# FT65E_SATA.net
KiCad netlist of a schematic drawn in Altium Designer
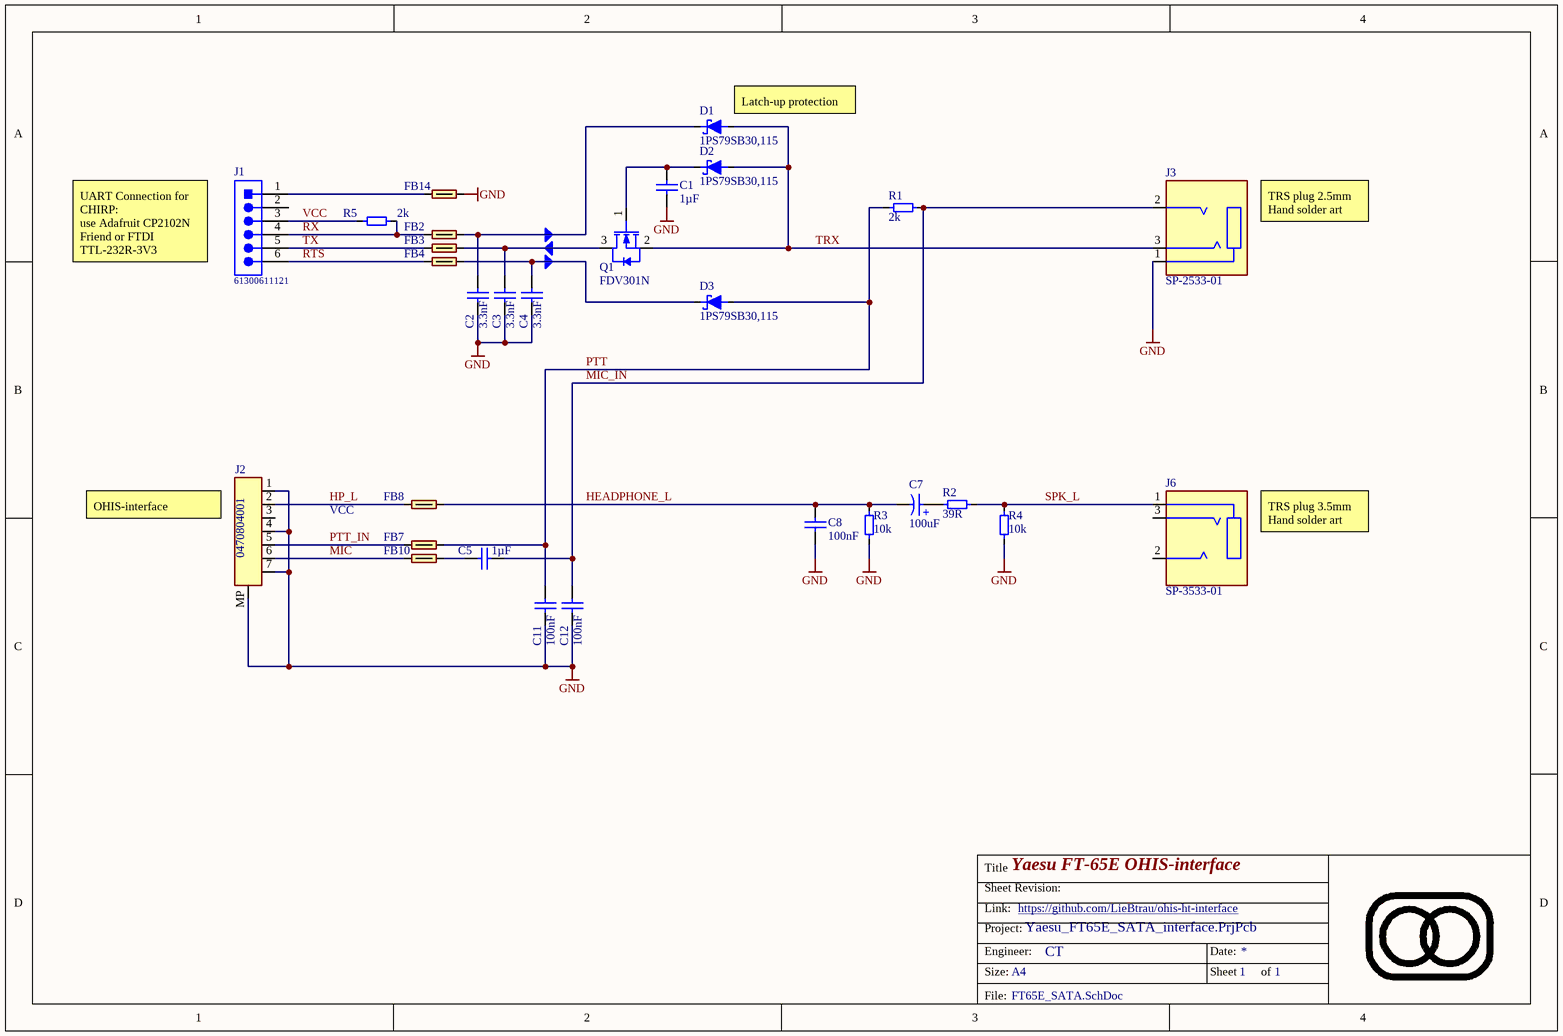
[diagram p0: FT65E_SATA.SchDoc]

(export (version "E")
  (design (tool "Eeschema 10.0.6"))
  (components
    (comp (ref "C1")
      (value "1µF")
      (footprint "0805-C-N")
      (description "WCAP-CSGP Multilayer Ceramic Chip Capacitor, General Purpose, size 0805, X7R, 1µF, 10VDC")
      (fields (field (name "TOLERANCE") "10%") (field (name "JLCPCB PART #") "C28323"))
      (libsource (lib "7c7 Engineering") (part "CAP-NP-2"))
    )
    (comp (ref "C2")
      (value "3.3nF")
      (footprint "0603-C-N")
      (description "WCAP-CSGP Multilayer Ceramic Chip Capacitor, General Purpose, size 0603, X7R, 3.3nF, 50VDC")
      (fields (field (name "TOLERANCE") "10%") (field (name "Comment") "Capacitor 3.3nF +/-10% 50V X7R 0603"))
      (libsource (lib "7c7 Engineering") (part "CAP-NP-2"))
    )
    (comp (ref "C3")
      (value "3.3nF")
      (footprint "0603-C-N")
      (description "WCAP-CSGP Multilayer Ceramic Chip Capacitor, General Purpose, size 0603, X7R, 3.3nF, 50VDC")
      (fields (field (name "TOLERANCE") "10%") (field (name "Comment") "Capacitor 3.3nF +/-10% 50V X7R 0603"))
      (libsource (lib "7c7 Engineering") (part "CAP-NP-2"))
    )
    (comp (ref "C4")
      (value "3.3nF")
      (footprint "0603-C-N")
      (description "WCAP-CSGP Multilayer Ceramic Chip Capacitor, General Purpose, size 0603, X7R, 3.3nF, 50VDC")
      (fields (field (name "TOLERANCE") "10%") (field (name "Comment") "Capacitor 3.3nF +/-10% 50V X7R 0603"))
      (libsource (lib "7c7 Engineering") (part "CAP-NP-2"))
    )
    (comp (ref "C5")
      (value "1µF")
      (footprint "0805-C-N")
      (description "WCAP-CSGP Multilayer Ceramic Chip Capacitor, General Purpose, size 0805, X7R, 1µF, 10VDC")
      (fields (field (name "TOLERANCE") "10%") (field (name "JLCPCB PART #") "C28323"))
      (libsource (lib "7c7 Engineering") (part "CAP-NP-2"))
    )
    (comp (ref "C7")
      (value "865080142007")
      (footprint "WCAP-ASLI_D5H5.5")
      (description "WCAP-ASLI Aluminum Electrolytic Capacitor, V-Chip, D5 x H5.5mm, 100uF, 6.3V")
      (fields (field (name "CAPACITANCE") "100uF") (field (name "MANUFACTURER") "Wurth Elektronik"))
      (libsource (lib "7c7 Engineering") (part "865081763011"))
    )
    (comp (ref "C8")
      (value "100nF")
      (footprint "0603-C-N")
      (description "Capacitor MLCC, General Purpose, size 0603, X7R, 100nF, +/-10%, 50V")
      (fields (field (name "JLCPCB PART #") "C14663") (field (name "TOLERANCE") "10%"))
      (libsource (lib "7c7 Engineering") (part "CAP-NP-2"))
    )
    (comp (ref "C11")
      (value "100nF")
      (footprint "0603-C-N")
      (description "Capacitor MLCC, General Purpose, size 0603, X7R, 100nF, +/-10%, 50V")
      (fields (field (name "JLCPCB PART #") "C14663") (field (name "TOLERANCE") "10%"))
      (libsource (lib "7c7 Engineering") (part "CAP-NP-2"))
    )
    (comp (ref "C12")
      (value "100nF")
      (footprint "0603-C-N")
      (description "Capacitor MLCC, General Purpose, size 0603, X7R, 100nF, +/-10%, 50V")
      (fields (field (name "JLCPCB PART #") "C14663") (field (name "TOLERANCE") "10%"))
      (libsource (lib "7c7 Engineering") (part "CAP-NP-2"))
    )
    (comp (ref "D1")
      (value "1PS79SB30,115")
      (footprint "FP-SOD523-MFG")
      (description "VR=40V IF=200mA 20pF")
      (fields (field (name "JLCPCB PART #") "C426690"))
      (libsource (lib "7c7 Engineering") (part "DIODE-SKY-2"))
    )
    (comp (ref "D2")
      (value "1PS79SB30,115")
      (footprint "FP-SOD523-MFG")
      (description "VR=40V IF=200mA 20pF")
      (fields (field (name "JLCPCB PART #") "C426690"))
      (libsource (lib "7c7 Engineering") (part "DIODE-SKY-2"))
    )
    (comp (ref "D3")
      (value "1PS79SB30,115")
      (footprint "FP-SOD523-MFG")
      (description "VR=40V IF=200mA 20pF")
      (fields (field (name "JLCPCB PART #") "C426690"))
      (libsource (lib "7c7 Engineering") (part "DIODE-SKY-2"))
    )
    (comp (ref "FB2")
      (value "742861210")
      (footprint "0603-FB-N")
      (description "Ferrite Beads Multi-Layer 1KOhm 25% 100MHz 50mA 1.8Ohm DCR 0603 T/R")
      (fields (field (name "TOLERANCE") "25%"))
      (libsource (lib "7c7 Engineering") (part "IND_BEAD"))
    )
    (comp (ref "FB3")
      (value "742861210")
      (footprint "0603-FB-N")
      (description "Ferrite Beads Multi-Layer 1KOhm 25% 100MHz 50mA 1.8Ohm DCR 0603 T/R")
      (fields (field (name "TOLERANCE") "25%"))
      (libsource (lib "7c7 Engineering") (part "IND_BEAD"))
    )
    (comp (ref "FB4")
      (value "742861210")
      (footprint "0603-FB-N")
      (description "Ferrite Beads Multi-Layer 1KOhm 25% 100MHz 50mA 1.8Ohm DCR 0603 T/R")
      (fields (field (name "TOLERANCE") "25%"))
      (libsource (lib "7c7 Engineering") (part "IND_BEAD"))
    )
    (comp (ref "FB7")
      (value "742861210")
      (footprint "0603-FB-N")
      (description "Ferrite Beads Multi-Layer 1KOhm 25% 100MHz 50mA 1.8Ohm DCR 0603 T/R")
      (fields (field (name "TOLERANCE") "25%"))
      (libsource (lib "7c7 Engineering") (part "IND_BEAD"))
    )
    (comp (ref "FB8")
      (value "742861210")
      (footprint "0603-FB-N")
      (description "Ferrite Beads Multi-Layer 1KOhm 25% 100MHz 50mA 1.8Ohm DCR 0603 T/R")
      (fields (field (name "TOLERANCE") "25%"))
      (libsource (lib "7c7 Engineering") (part "IND_BEAD"))
    )
    (comp (ref "FB10")
      (value "742861210")
      (footprint "0603-FB-N")
      (description "Ferrite Beads Multi-Layer 1KOhm 25% 100MHz 50mA 1.8Ohm DCR 0603 T/R")
      (fields (field (name "TOLERANCE") "25%"))
      (libsource (lib "7c7 Engineering") (part "IND_BEAD"))
    )
    (comp (ref "FB14")
      (value "742861210")
      (footprint "0603-FB-N")
      (description "Ferrite Beads Multi-Layer 1KOhm 25% 100MHz 50mA 1.8Ohm DCR 0603 T/R")
      (fields (field (name "TOLERANCE") "25%"))
      (libsource (lib "7c7 Engineering") (part "IND_BEAD"))
    )
    (comp (ref "J1")
      (value "61300611121")
      (footprint "61300611121")
      (description "WR-PHD Pin Header, THT, pitch 2.54mm, Single Row, Vertical, 6p")
      (fields (field (name "MANUFACTURER") "Wurth Elektronik"))
      (libsource (lib "7c7 Engineering") (part "Symbol"))
    )
    (comp (ref "J2")
      (value "0470804001")
      (footprint "0470804001-Footprint-1")
      (description "Header Connector, pcb Mount, recept, 7 Contacts, pin, 0.05 Pitch, surface Mount Terminal, locking")
      (fields (field (name "JLCPCB PART #") "C587821"))
      (libsource (lib "7c7 Engineering") (part "CN_HDR_1x7P"))
    )
    (comp (ref "J3")
      (value "SP-2533-01")
      (footprint "SP-2533-01-Footprint-1")
      (description "2.5 mm, Stereo, Overmold, Audio Plug Connector")
      (libsource (lib "") (part "CN_AUDIO_JACK_TRS_NO_SWITCH_1"))
    )
    (comp (ref "J6")
      (value "SP-3533-01")
      (footprint "SP-3533-01-Footprint-1")
      (description "3.5 mm, Stereo, Overmold, Audio Plug Connector")
      (libsource (lib "7c7 Engineering") (part "CN_AUDIO_JACK_TRS_NO_SWITCH"))
    )
    (comp (ref "Q1")
      (value "FDV301N")
      (footprint "SOT-23-3-N")
      (description "Transistor MOSFET N-Ch. 25V 220mA 0, 35W 4Ohm SOT23")
      (fields (field (name "JLCPCB PART #") "C15310"))
      (libsource (lib "7c7 Engineering") (part "NEMOS-GSD-3"))
    )
    (comp (ref "R1")
      (value "2k")
      (footprint "0603-R-N")
      (description "Chip Resistor, Thick Film, General Purpose, 0603, 100mW, 50V, 2 kOhm, +/-1%")
      (fields (field (name "JLCPCB PART #") "C22975") (field (name "TOLERANCE") "1%"))
      (libsource (lib "") (part "RES_1"))
    )
    (comp (ref "R2")
      (value "39R")
      (footprint "0603-R-N")
      (description "SMD Chip Resistor, 39 Ohm, ± 1%, 100 mW, 0603 [1608 Metric], Thick Film, General Purpose")
      (fields (field (name "TOLERANCE") "1%") (field (name "JLCPCB PART #") "C2907161"))
      (libsource (lib "") (part "RES_1"))
    )
    (comp (ref "R3")
      (value "10k")
      (footprint "0603-R-N")
      (description "Chip Resistor, Thick Film, General Purpose, 0603, 100mW, 50V, 10 kOhm, +/-1%")
      (fields (field (name "JLCPCB PART #") "C25804") (field (name "TOLERANCE") "1%"))
      (libsource (lib "7c7 Engineering") (part "RES"))
    )
    (comp (ref "R4")
      (value "10k")
      (footprint "0603-R-N")
      (description "Chip Resistor, Thick Film, General Purpose, 0603, 100mW, 50V, 10 kOhm, +/-1%")
      (fields (field (name "JLCPCB PART #") "C25804") (field (name "TOLERANCE") "1%"))
      (libsource (lib "7c7 Engineering") (part "RES"))
    )
    (comp (ref "R5")
      (value "2k")
      (footprint "0603-R-N")
      (description "Chip Resistor, Thick Film, General Purpose, 0603, 100mW, 50V, 2 kOhm, +/-1%")
      (fields (field (name "JLCPCB PART #") "C22975") (field (name "TOLERANCE") "1%"))
      (libsource (lib "") (part "RES_1"))
    )
  )
  (nets
    (net (code "1") (name "/HEADPHONE_L") (class "Default")
      (node (ref "C7") (pin "2") (pinfunction "N_2") (pintype "passive"))
      (node (ref "C8") (pin "2") (pinfunction "2_2") (pintype "passive"))
      (node (ref "FB8") (pin "2") (pinfunction "2_2") (pintype "passive"))
      (node (ref "R3") (pin "2") (pinfunction "2_2") (pintype "passive"))
    )
    (net (code "2") (name "/HP_L") (class "Default")
      (node (ref "FB8") (pin "1") (pinfunction "1_1") (pintype "passive"))
      (node (ref "J2") (pin "2") (pinfunction "2_2") (pintype "power_in"))
    )
    (net (code "3") (name "/MIC") (class "Default")
      (node (ref "FB10") (pin "1") (pinfunction "1_1") (pintype "passive"))
      (node (ref "J2") (pin "6") (pinfunction "6_6") (pintype "power_in"))
    )
    (net (code "4") (name "/MIC_IN") (class "Default")
      (node (ref "C12") (pin "2") (pinfunction "2_2") (pintype "passive"))
      (node (ref "C5") (pin "1") (pinfunction "1_1") (pintype "passive"))
      (node (ref "J3") (pin "2") (pinfunction "2_2") (pintype "passive"))
      (node (ref "R1") (pin "2") (pinfunction "2_2") (pintype "passive"))
    )
    (net (code "5") (name "/PTT") (class "Default")
      (node (ref "C11") (pin "2") (pinfunction "2_2") (pintype "passive"))
      (node (ref "D3") (pin "2") (pinfunction "A_2") (pintype "passive"))
      (node (ref "FB7") (pin "2") (pinfunction "2_2") (pintype "passive"))
      (node (ref "R1") (pin "1") (pinfunction "1_1") (pintype "passive"))
    )
    (net (code "6") (name "/PTT_IN") (class "Default")
      (node (ref "FB7") (pin "1") (pinfunction "1_1") (pintype "passive"))
      (node (ref "J2") (pin "5") (pinfunction "5_5") (pintype "power_in"))
    )
    (net (code "7") (name "/RTS") (class "Default")
      (node (ref "FB4") (pin "1") (pinfunction "1_1") (pintype "passive"))
      (node (ref "J1") (pin "6") (pinfunction "6_6") (pintype "passive"))
    )
    (net (code "8") (name "/RX") (class "Default")
      (node (ref "FB2") (pin "1") (pinfunction "1_1") (pintype "passive"))
      (node (ref "J1") (pin "4") (pinfunction "4_4") (pintype "passive"))
      (node (ref "R5") (pin "2") (pinfunction "2_2") (pintype "passive"))
    )
    (net (code "9") (name "/SPK_L") (class "Default")
      (node (ref "J6") (pin "1") (pinfunction "1_1") (pintype "passive"))
      (node (ref "R2") (pin "2") (pinfunction "2_2") (pintype "passive"))
      (node (ref "R4") (pin "2") (pinfunction "2_2") (pintype "passive"))
    )
    (net (code "10") (name "/TRX") (class "Default")
      (node (ref "D1") (pin "2") (pinfunction "A_2") (pintype "passive"))
      (node (ref "D2") (pin "2") (pinfunction "A_2") (pintype "passive"))
      (node (ref "J3") (pin "3") (pinfunction "3_3") (pintype "passive"))
      (node (ref "Q1") (pin "2") (pinfunction "S_2") (pintype "passive"))
    )
    (net (code "11") (name "/TX") (class "Default")
      (node (ref "FB3") (pin "1") (pinfunction "1_1") (pintype "passive"))
      (node (ref "J1") (pin "5") (pinfunction "5_5") (pintype "passive"))
    )
    (net (code "12") (name "/VCC") (class "Default")
      (node (ref "J1") (pin "3") (pinfunction "3_3") (pintype "passive"))
      (node (ref "R5") (pin "1") (pinfunction "1_1") (pintype "passive"))
    )
    (net (code "13") (name "GND") (class "Default")
      (node (ref "C1") (pin "1") (pinfunction "1_1") (pintype "passive"))
      (node (ref "C11") (pin "1") (pinfunction "1_1") (pintype "passive"))
      (node (ref "C12") (pin "1") (pinfunction "1_1") (pintype "passive"))
      (node (ref "C2") (pin "1") (pinfunction "1_1") (pintype "passive"))
      (node (ref "C3") (pin "1") (pinfunction "1_1") (pintype "passive"))
      (node (ref "C4") (pin "1") (pinfunction "1_1") (pintype "passive"))
      (node (ref "C8") (pin "1") (pinfunction "1_1") (pintype "passive"))
      (node (ref "FB14") (pin "2") (pinfunction "2_2") (pintype "passive"))
      (node (ref "J2") (pin "1") (pinfunction "1_1") (pintype "power_in"))
      (node (ref "J2") (pin "4") (pinfunction "4_4") (pintype "power_in"))
      (node (ref "J2") (pin "7") (pinfunction "7_7") (pintype "power_in"))
      (node (ref "J2") (pin "MP") (pinfunction "MP_MP") (pintype "power_in"))
      (node (ref "J3") (pin "1") (pinfunction "1_1") (pintype "passive"))
      (node (ref "R3") (pin "1") (pinfunction "1_1") (pintype "passive"))
      (node (ref "R4") (pin "1") (pinfunction "1_1") (pintype "passive"))
    )
    (net (code "14") (name "Net-(C5-Pad2)") (class "Default")
      (node (ref "C5") (pin "2") (pinfunction "2_2") (pintype "passive"))
      (node (ref "FB10") (pin "2") (pinfunction "2_2") (pintype "passive"))
    )
    (net (code "15") (name "Net-(C7-P)") (class "Default")
      (node (ref "C7") (pin "1") (pinfunction "P_1") (pintype "passive"))
      (node (ref "R2") (pin "1") (pinfunction "1_1") (pintype "passive"))
    )
    (net (code "16") (name "Net-(D1-K)") (class "Default")
      (node (ref "C2") (pin "2") (pinfunction "2_2") (pintype "passive"))
      (node (ref "D1") (pin "1") (pinfunction "K_1") (pintype "passive"))
      (node (ref "FB2") (pin "2") (pinfunction "2_2") (pintype "passive"))
    )
    (net (code "17") (name "Net-(D2-K)") (class "Default")
      (node (ref "C1") (pin "2") (pinfunction "2_2") (pintype "passive"))
      (node (ref "D2") (pin "1") (pinfunction "K_1") (pintype "passive"))
      (node (ref "Q1") (pin "1") (pinfunction "G_1") (pintype "passive"))
    )
    (net (code "18") (name "Net-(D3-K)") (class "Default")
      (node (ref "C4") (pin "2") (pinfunction "2_2") (pintype "passive"))
      (node (ref "D3") (pin "1") (pinfunction "K_1") (pintype "passive"))
      (node (ref "FB4") (pin "2") (pinfunction "2_2") (pintype "passive"))
    )
    (net (code "19") (name "Net-(FB14-Pad1)") (class "Default")
      (node (ref "FB14") (pin "1") (pinfunction "1_1") (pintype "passive"))
      (node (ref "J1") (pin "1") (pinfunction "1_1") (pintype "passive"))
    )
    (net (code "20") (name "Net-(Q1-D)") (class "Default")
      (node (ref "C3") (pin "2") (pinfunction "2_2") (pintype "passive"))
      (node (ref "FB3") (pin "2") (pinfunction "2_2") (pintype "passive"))
      (node (ref "Q1") (pin "3") (pinfunction "D_3") (pintype "passive"))
    )
    (net (code "21") (name "unconnected-(J1-Pad2)") (class "Default")
      (node (ref "J1") (pin "2") (pinfunction "2_2") (pintype "passive"))
    )
    (net (code "22") (name "unconnected-(J2-Pad3)") (class "Default")
      (node (ref "J2") (pin "3") (pinfunction "3_3") (pintype "power_in"))
    )
    (net (code "23") (name "unconnected-(J6-Pad2)") (class "Default")
      (node (ref "J6") (pin "2") (pinfunction "2_2") (pintype "passive"))
    )
    (net (code "24") (name "unconnected-(J6-Pad3)") (class "Default")
      (node (ref "J6") (pin "3") (pinfunction "3_3") (pintype "passive"))
    )
  )
)
